# llrf_afe_mfm_rio.net
KiCad netlist of a schematic drawn in Altium Designer
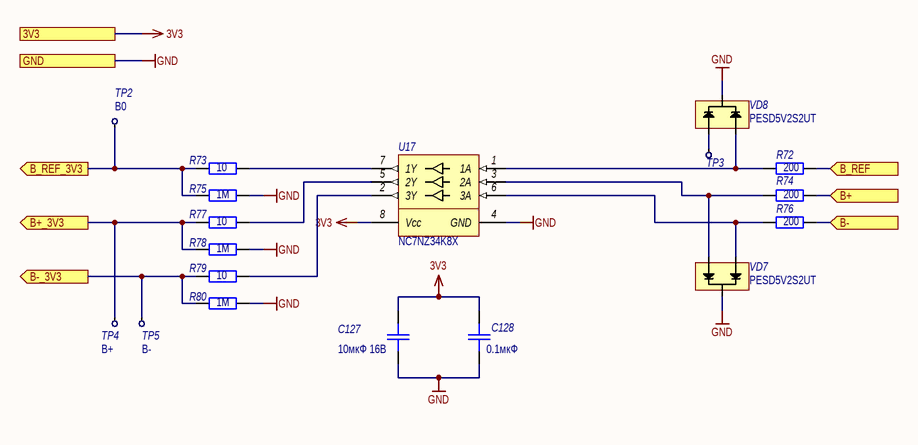
[diagram p0: llrf_afe_mfm_rio.SchDoc]

(export (version "E")
  (design (tool "Eeschema 10.0.6"))
  (components
    (comp (ref "C127")
      (value "10мкФ 16В")
      (footprint "SMD_C0603")
      (description "Capacitor")
      (libsource (lib "Passive") (part "Capacitor"))
    )
    (comp (ref "C128")
      (value "0.1мкФ")
      (footprint "SMD_C0402")
      (description "Capacitor")
      (libsource (lib "Passive") (part "Capacitor"))
    )
    (comp (ref "R72")
      (value "200")
      (footprint "SMD_0603")
      (description "Resistor")
      (libsource (lib "Passive") (part "Resistor"))
    )
    (comp (ref "R73")
      (value "10")
      (footprint "SMD_0603")
      (description "Resistor")
      (libsource (lib "Passive") (part "Resistor"))
    )
    (comp (ref "R74")
      (value "200")
      (footprint "SMD_0603")
      (description "Resistor")
      (libsource (lib "Passive") (part "Resistor"))
    )
    (comp (ref "R75")
      (value "1M")
      (footprint "SMD_0603")
      (description "Resistor")
      (libsource (lib "") (part "Resistor_1"))
    )
    (comp (ref "R76")
      (value "200")
      (footprint "SMD_0603")
      (description "Resistor")
      (libsource (lib "Passive") (part "Resistor"))
    )
    (comp (ref "R77")
      (value "10")
      (footprint "SMD_0603")
      (description "Resistor")
      (libsource (lib "Passive") (part "Resistor"))
    )
    (comp (ref "R78")
      (value "1M")
      (footprint "SMD_0603")
      (description "Resistor")
      (libsource (lib "") (part "Resistor_1"))
    )
    (comp (ref "R79")
      (value "10")
      (footprint "SMD_0603")
      (description "Resistor")
      (libsource (lib "Passive") (part "Resistor"))
    )
    (comp (ref "R80")
      (value "1M")
      (footprint "SMD_0603")
      (description "Resistor")
      (libsource (lib "") (part "Resistor_1"))
    )
    (comp (ref "TP2")
      (value "B0")
      (footprint "TestPoint")
      (fields (field (name "TP_NAME") "B0"))
      (libsource (lib "Connector") (part "TP"))
    )
    (comp (ref "TP3") (value "~") (footprint "TestPoint") (libsource (lib "Connector") (part "TP")))
    (comp (ref "TP4")
      (value "B+")
      (footprint "TestPoint")
      (fields (field (name "TP_NAME") "B+"))
      (libsource (lib "Connector") (part "TP"))
    )
    (comp (ref "TP5")
      (value "B-")
      (footprint "TestPoint")
      (fields (field (name "TP_NAME") "B-"))
      (libsource (lib "Connector") (part "TP"))
    )
    (comp (ref "U17")
      (value "NC7NZ34")
      (footprint "US-8")
      (description "TinyLogic UHS Triple Buffer")
      (fields (field (name "НАИМЕНОВАНИЕ") "NC7NZ34K8X"))
      (libsource (lib "Logic") (part "NC7NZ34"))
    )
    (comp (ref "VD7")
      (value "PESDxS2UT")
      (footprint "SOT-23")
      (description "Double ESD protection diodes")
      (fields (field (name "НАИМЕНОВАНИЕ") "PESD5V2S2UT"))
      (libsource (lib "PESDxS2UT") (part "PESDxS2UT"))
    )
    (comp (ref "VD8")
      (value "PESDxS2UT")
      (footprint "SOT-23")
      (description "Double ESD protection diodes")
      (fields (field (name "НАИМЕНОВАНИЕ") "PESD5V2S2UT"))
      (libsource (lib "") (part "PESDxS2UT_1"))
    )
  )
  (nets
    (net (code "1") (name "/B+") (class "Default")
      (node (ref "R74") (pin "2") (pinfunction "2_2") (pintype "passive"))
    )
    (net (code "2") (name "/B+_3V3") (class "Default")
      (node (ref "R77") (pin "1") (pinfunction "1_1") (pintype "passive"))
      (node (ref "R78") (pin "2") (pinfunction "2_2") (pintype "passive"))
      (node (ref "TP4") (pin "0") (pinfunction "TP_0") (pintype "passive"))
    )
    (net (code "3") (name "/B-") (class "Default")
      (node (ref "R76") (pin "2") (pinfunction "2_2") (pintype "passive"))
    )
    (net (code "4") (name "/B-_3V3") (class "Default")
      (node (ref "R79") (pin "1") (pinfunction "1_1") (pintype "passive"))
      (node (ref "R80") (pin "2") (pinfunction "2_2") (pintype "passive"))
      (node (ref "TP5") (pin "0") (pinfunction "TP_0") (pintype "passive"))
    )
    (net (code "5") (name "/B_REF") (class "Default")
      (node (ref "R72") (pin "2") (pinfunction "2_2") (pintype "passive"))
    )
    (net (code "6") (name "/B_REF_3V3") (class "Default")
      (node (ref "R73") (pin "1") (pinfunction "1_1") (pintype "passive"))
      (node (ref "R75") (pin "2") (pinfunction "2_2") (pintype "passive"))
      (node (ref "TP2") (pin "0") (pinfunction "TP_0") (pintype "passive"))
    )
    (net (code "7") (name "3V3") (class "Default")
      (node (ref "C127") (pin "2") (pinfunction "2_2") (pintype "passive"))
      (node (ref "C128") (pin "2") (pinfunction "2_2") (pintype "passive"))
      (node (ref "U17") (pin "8") (pinfunction "Vcc_8") (pintype "power_in"))
    )
    (net (code "8") (name "GND") (class "Default")
      (node (ref "C127") (pin "1") (pinfunction "1_1") (pintype "passive"))
      (node (ref "C128") (pin "1") (pinfunction "1_1") (pintype "passive"))
      (node (ref "R75") (pin "1") (pinfunction "1_1") (pintype "passive"))
      (node (ref "R78") (pin "1") (pinfunction "1_1") (pintype "passive"))
      (node (ref "R80") (pin "1") (pinfunction "1_1") (pintype "passive"))
      (node (ref "U17") (pin "4") (pinfunction "GND_4") (pintype "power_in"))
      (node (ref "VD7") (pin "3") (pinfunction "C3_3") (pintype "passive"))
      (node (ref "VD8") (pin "3") (pinfunction "C3_3") (pintype "passive"))
    )
    (net (code "9") (name "Net-(TP3-TP)") (class "Default")
      (node (ref "TP3") (pin "0") (pinfunction "TP_0") (pintype "passive"))
      (node (ref "VD8") (pin "2") (pinfunction "C2_2") (pintype "passive"))
    )
    (net (code "10") (name "Net-(U17-1A)") (class "Default")
      (node (ref "R72") (pin "1") (pinfunction "1_1") (pintype "passive"))
      (node (ref "U17") (pin "1") (pinfunction "1A_1") (pintype "input"))
      (node (ref "VD8") (pin "1") (pinfunction "C1_1") (pintype "passive"))
    )
    (net (code "11") (name "Net-(U17-1Y)") (class "Default")
      (node (ref "R73") (pin "2") (pinfunction "2_2") (pintype "passive"))
      (node (ref "U17") (pin "7") (pinfunction "1Y_7") (pintype "output"))
    )
    (net (code "12") (name "Net-(U17-2A)") (class "Default")
      (node (ref "R74") (pin "1") (pinfunction "1_1") (pintype "passive"))
      (node (ref "U17") (pin "3") (pinfunction "2A_3") (pintype "input"))
      (node (ref "VD7") (pin "1") (pinfunction "C1_1") (pintype "passive"))
    )
    (net (code "13") (name "Net-(U17-2Y)") (class "Default")
      (node (ref "R77") (pin "2") (pinfunction "2_2") (pintype "passive"))
      (node (ref "U17") (pin "5") (pinfunction "2Y_5") (pintype "output"))
    )
    (net (code "14") (name "Net-(U17-3A)") (class "Default")
      (node (ref "R76") (pin "1") (pinfunction "1_1") (pintype "passive"))
      (node (ref "U17") (pin "6") (pinfunction "3A_6") (pintype "input"))
      (node (ref "VD7") (pin "2") (pinfunction "C2_2") (pintype "passive"))
    )
    (net (code "15") (name "Net-(U17-3Y)") (class "Default")
      (node (ref "R79") (pin "2") (pinfunction "2_2") (pintype "passive"))
      (node (ref "U17") (pin "2") (pinfunction "3Y_2") (pintype "output"))
    )
  )
)
